# pixhawk.net
KiCad netlist of a schematic drawn in EAGLE
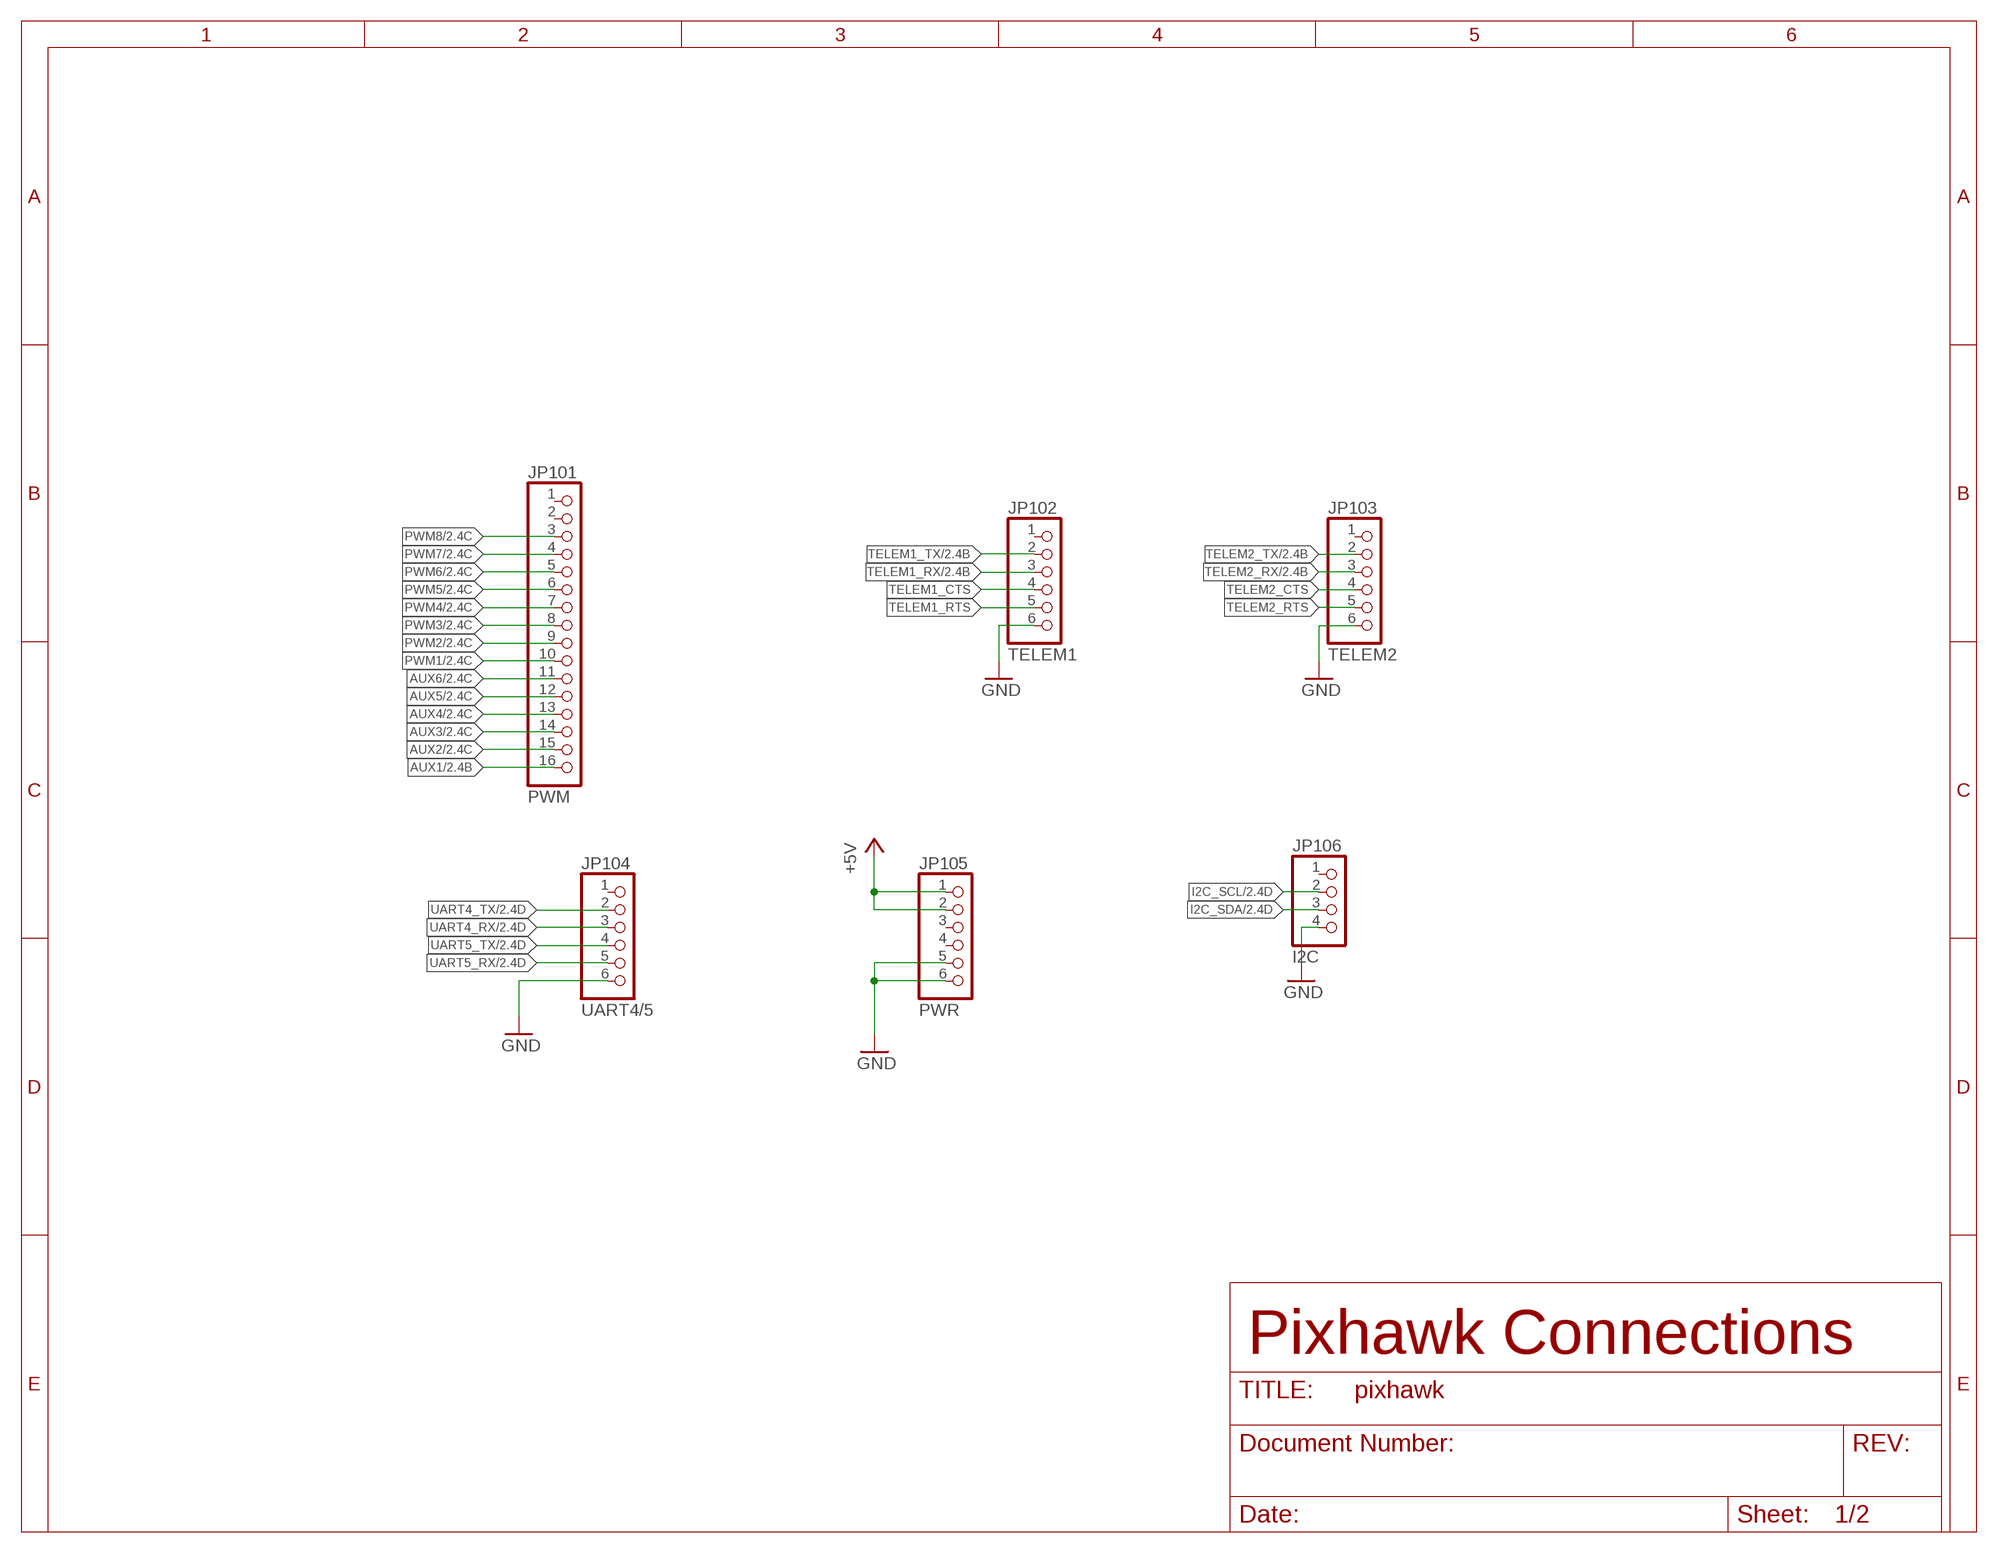
[diagram p0: schematic, sheet 1]
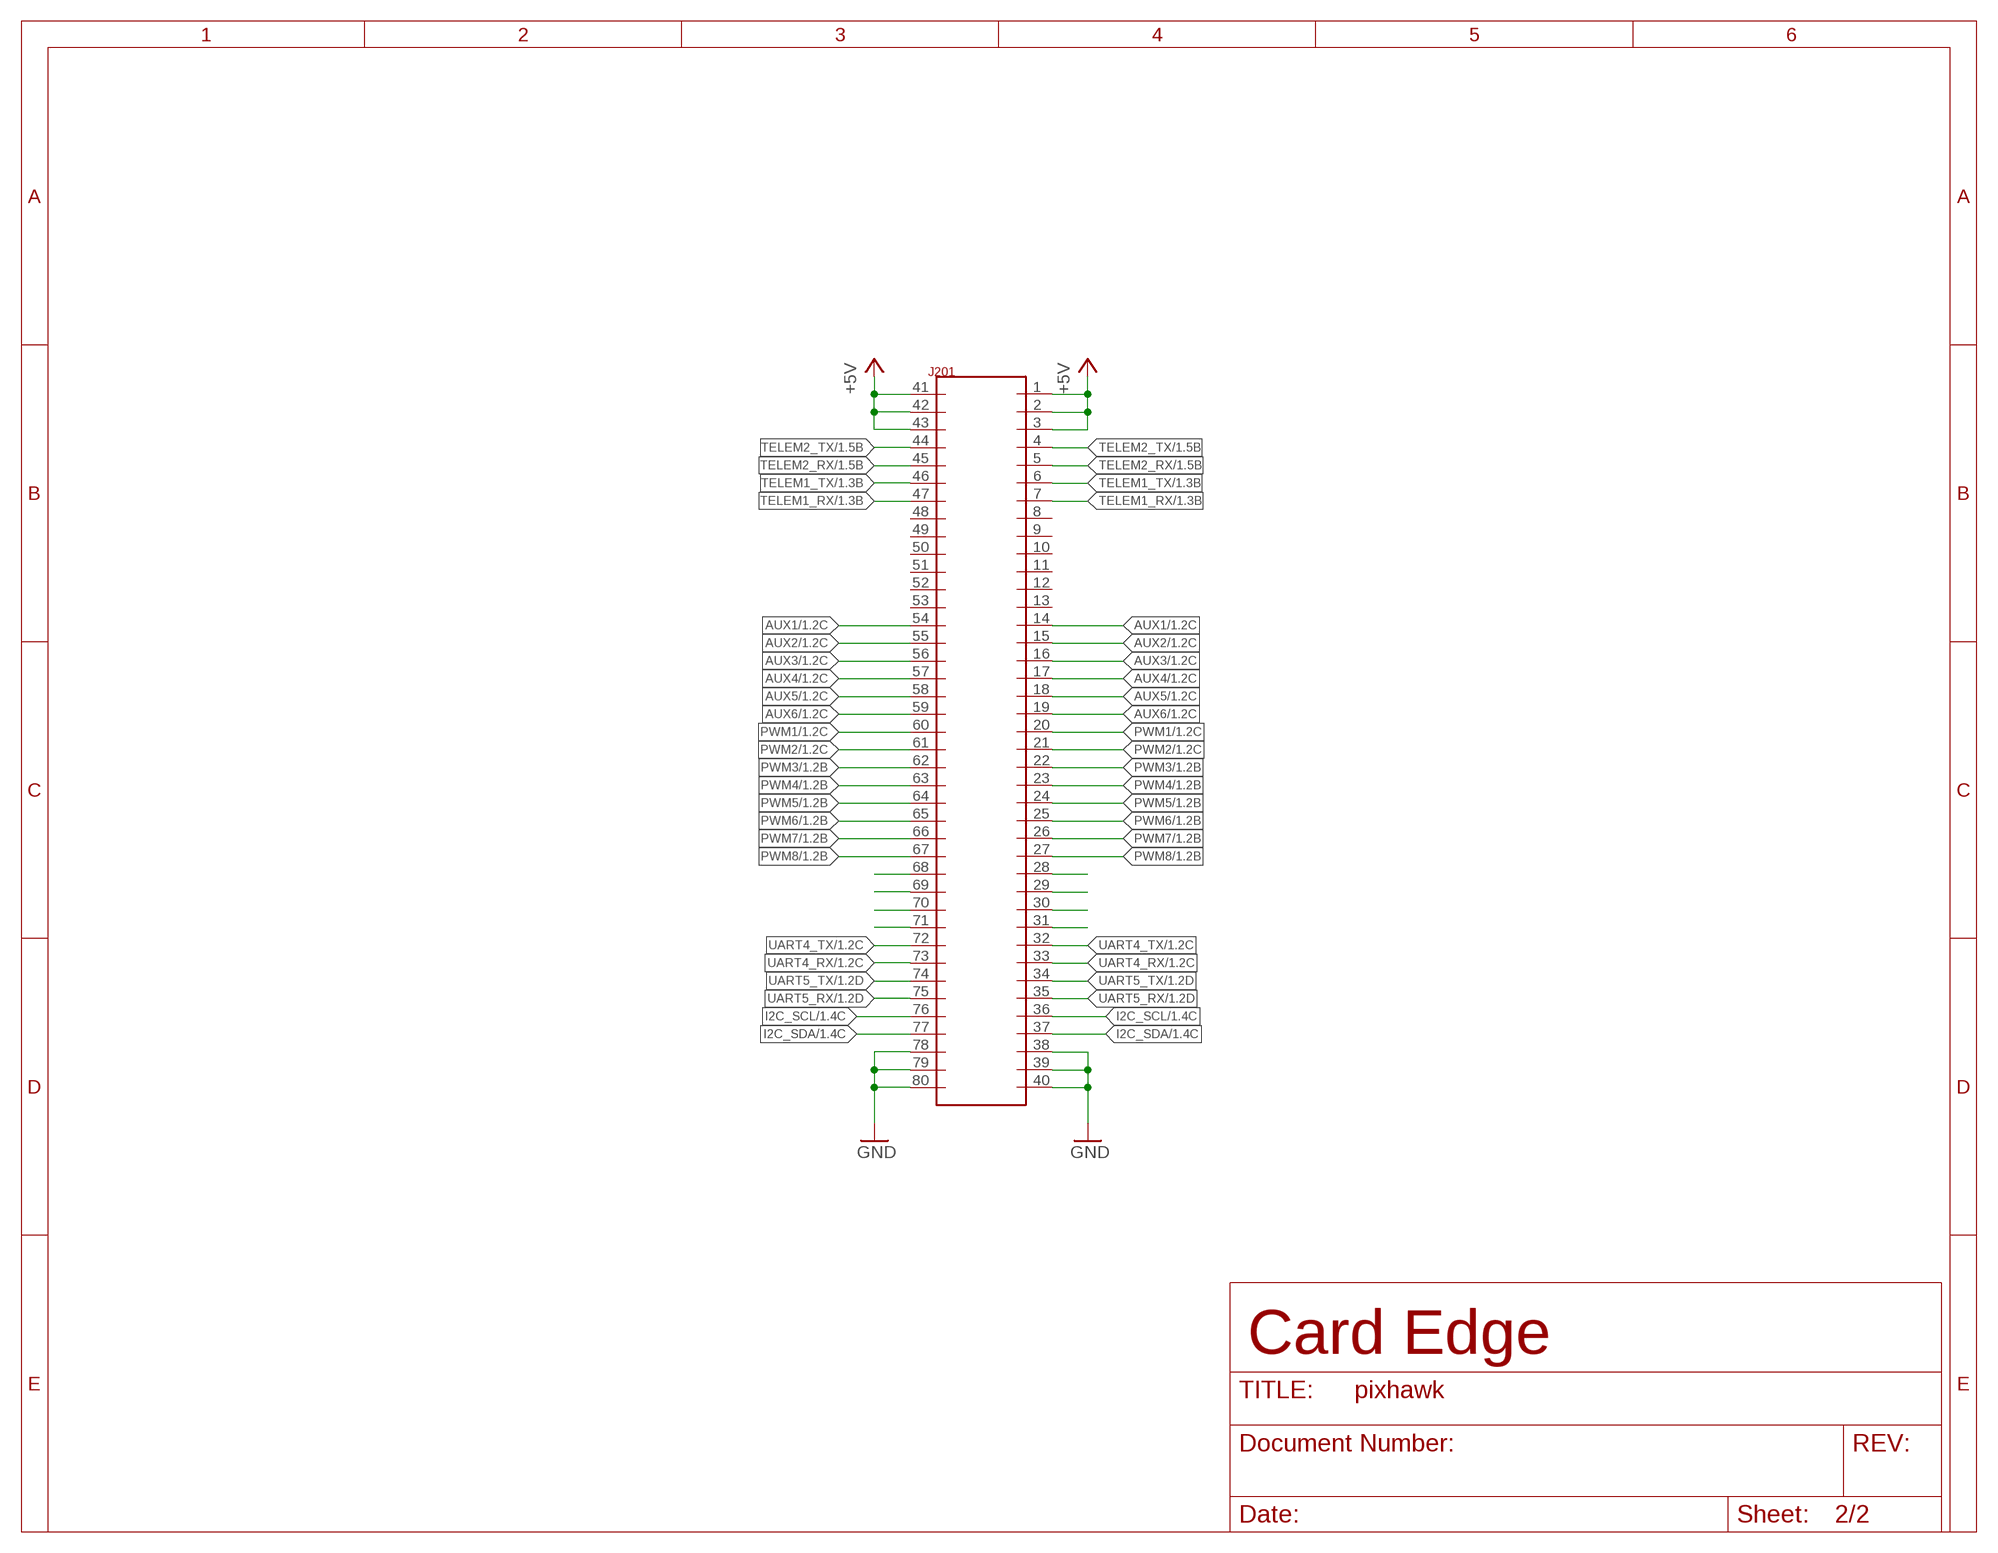
[diagram p1: schematic, sheet 2]

(export (version "E")
  (design (tool "Eeschema 10.0.6"))
  (components
    (comp (ref "J201")
      (value "80-PIN-CARD-EDGE")
      (footprint "eagle-import:80-PIN-CARD-EDGE")
      (libsource (lib "eagle-import") (part "80-PIN-CARD-EDGE"))
    )
    (comp (ref "JP101")
      (value "PWM")
      (footprint "eagle-import:1X16")
      (libsource (lib "eagle-import") (part "PINHD-1X16"))
    )
    (comp (ref "JP102")
      (value "TELEM1")
      (footprint "eagle-import:1X06")
      (libsource (lib "eagle-import") (part "PINHD-1X6"))
    )
    (comp (ref "JP103")
      (value "TELEM2")
      (footprint "eagle-import:1X06")
      (libsource (lib "eagle-import") (part "PINHD-1X6"))
    )
    (comp (ref "JP104")
      (value "UART4/5")
      (footprint "eagle-import:1X06")
      (libsource (lib "eagle-import") (part "PINHD-1X6"))
    )
    (comp (ref "JP105")
      (value "PWR")
      (footprint "eagle-import:1X06")
      (libsource (lib "eagle-import") (part "PINHD-1X6"))
    )
    (comp (ref "JP106")
      (value "I2C")
      (footprint "eagle-import:1X04")
      (libsource (lib "eagle-import") (part "PINHD-1X4"))
    )
  )
  (nets
    (net (code "1") (name "+5V") (class "Default")
      (node (ref "J201") (pin "1") (pinfunction "P$1_1") (pintype "bidirectional"))
      (node (ref "J201") (pin "2") (pinfunction "P$2_2") (pintype "bidirectional"))
      (node (ref "J201") (pin "3") (pinfunction "P$3_3") (pintype "bidirectional"))
      (node (ref "J201") (pin "41") (pinfunction "P$41_41") (pintype "bidirectional"))
      (node (ref "J201") (pin "42") (pinfunction "P$42_42") (pintype "bidirectional"))
      (node (ref "J201") (pin "43") (pinfunction "P$43_43") (pintype "bidirectional"))
      (node (ref "JP105") (pin "1") (pinfunction "1_1") (pintype "passive"))
      (node (ref "JP105") (pin "2") (pinfunction "2_2") (pintype "passive"))
    )
    (net (code "2") (name "AUX1") (class "Default")
      (node (ref "J201") (pin "14") (pinfunction "P$14_14") (pintype "bidirectional"))
      (node (ref "J201") (pin "54") (pinfunction "P$54_54") (pintype "bidirectional"))
      (node (ref "JP101") (pin "16") (pinfunction "16_16") (pintype "passive"))
    )
    (net (code "3") (name "AUX2") (class "Default")
      (node (ref "J201") (pin "15") (pinfunction "P$15_15") (pintype "bidirectional"))
      (node (ref "J201") (pin "55") (pinfunction "P$55_55") (pintype "bidirectional"))
      (node (ref "JP101") (pin "15") (pinfunction "15_15") (pintype "passive"))
    )
    (net (code "4") (name "AUX3") (class "Default")
      (node (ref "J201") (pin "16") (pinfunction "P$16_16") (pintype "bidirectional"))
      (node (ref "J201") (pin "56") (pinfunction "P$56_56") (pintype "bidirectional"))
      (node (ref "JP101") (pin "14") (pinfunction "14_14") (pintype "passive"))
    )
    (net (code "5") (name "AUX4") (class "Default")
      (node (ref "J201") (pin "17") (pinfunction "P$17_17") (pintype "bidirectional"))
      (node (ref "J201") (pin "57") (pinfunction "P$57_57") (pintype "bidirectional"))
      (node (ref "JP101") (pin "13") (pinfunction "13_13") (pintype "passive"))
    )
    (net (code "6") (name "AUX5") (class "Default")
      (node (ref "J201") (pin "18") (pinfunction "P$18_18") (pintype "bidirectional"))
      (node (ref "J201") (pin "58") (pinfunction "P$58_58") (pintype "bidirectional"))
      (node (ref "JP101") (pin "12") (pinfunction "12_12") (pintype "passive"))
    )
    (net (code "7") (name "AUX6") (class "Default")
      (node (ref "J201") (pin "19") (pinfunction "P$19_19") (pintype "bidirectional"))
      (node (ref "J201") (pin "59") (pinfunction "P$59_59") (pintype "bidirectional"))
      (node (ref "JP101") (pin "11") (pinfunction "11_11") (pintype "passive"))
    )
    (net (code "8") (name "CAN_H") (class "Default")
      (node (ref "J201") (pin "30") (pinfunction "P$30_30") (pintype "bidirectional"))
      (node (ref "J201") (pin "70") (pinfunction "P$70_70") (pintype "bidirectional"))
    )
    (net (code "9") (name "CAN_L") (class "Default")
      (node (ref "J201") (pin "31") (pinfunction "P$31_31") (pintype "bidirectional"))
      (node (ref "J201") (pin "71") (pinfunction "P$71_71") (pintype "bidirectional"))
    )
    (net (code "10") (name "GND") (class "Default")
      (node (ref "J201") (pin "38") (pinfunction "P$38_38") (pintype "bidirectional"))
      (node (ref "J201") (pin "39") (pinfunction "P$39_39") (pintype "bidirectional"))
      (node (ref "J201") (pin "40") (pinfunction "P$40_40") (pintype "bidirectional"))
      (node (ref "J201") (pin "78") (pinfunction "P$78_78") (pintype "bidirectional"))
      (node (ref "J201") (pin "79") (pinfunction "P$79_79") (pintype "bidirectional"))
      (node (ref "J201") (pin "80") (pinfunction "P$80_80") (pintype "bidirectional"))
      (node (ref "JP102") (pin "6") (pinfunction "6_6") (pintype "passive"))
      (node (ref "JP103") (pin "6") (pinfunction "6_6") (pintype "passive"))
      (node (ref "JP104") (pin "6") (pinfunction "6_6") (pintype "passive"))
      (node (ref "JP105") (pin "5") (pinfunction "5_5") (pintype "passive"))
      (node (ref "JP105") (pin "6") (pinfunction "6_6") (pintype "passive"))
      (node (ref "JP106") (pin "4") (pinfunction "4_4") (pintype "passive"))
    )
    (net (code "11") (name "I2C_SCL") (class "Default")
      (node (ref "J201") (pin "36") (pinfunction "P$36_36") (pintype "bidirectional"))
      (node (ref "J201") (pin "76") (pinfunction "P$76_76") (pintype "bidirectional"))
      (node (ref "JP106") (pin "2") (pinfunction "2_2") (pintype "passive"))
    )
    (net (code "12") (name "I2C_SDA") (class "Default")
      (node (ref "J201") (pin "37") (pinfunction "P$37_37") (pintype "bidirectional"))
      (node (ref "J201") (pin "77") (pinfunction "P$77_77") (pintype "bidirectional"))
      (node (ref "JP106") (pin "3") (pinfunction "3_3") (pintype "passive"))
    )
    (net (code "13") (name "PWM1") (class "Default")
      (node (ref "J201") (pin "20") (pinfunction "P$20_20") (pintype "bidirectional"))
      (node (ref "J201") (pin "60") (pinfunction "P$60_60") (pintype "bidirectional"))
      (node (ref "JP101") (pin "10") (pinfunction "10_10") (pintype "passive"))
    )
    (net (code "14") (name "PWM2") (class "Default")
      (node (ref "J201") (pin "21") (pinfunction "P$21_21") (pintype "bidirectional"))
      (node (ref "J201") (pin "61") (pinfunction "P$61_61") (pintype "bidirectional"))
      (node (ref "JP101") (pin "9") (pinfunction "9_9") (pintype "passive"))
    )
    (net (code "15") (name "PWM3") (class "Default")
      (node (ref "J201") (pin "22") (pinfunction "P$22_22") (pintype "bidirectional"))
      (node (ref "J201") (pin "62") (pinfunction "P$62_62") (pintype "bidirectional"))
      (node (ref "JP101") (pin "8") (pinfunction "8_8") (pintype "passive"))
    )
    (net (code "16") (name "PWM4") (class "Default")
      (node (ref "J201") (pin "23") (pinfunction "P$23_23") (pintype "bidirectional"))
      (node (ref "J201") (pin "63") (pinfunction "P$63_63") (pintype "bidirectional"))
      (node (ref "JP101") (pin "7") (pinfunction "7_7") (pintype "passive"))
    )
    (net (code "17") (name "PWM5") (class "Default")
      (node (ref "J201") (pin "24") (pinfunction "P$24_24") (pintype "bidirectional"))
      (node (ref "J201") (pin "64") (pinfunction "P$64_64") (pintype "bidirectional"))
      (node (ref "JP101") (pin "6") (pinfunction "6_6") (pintype "passive"))
    )
    (net (code "18") (name "PWM6") (class "Default")
      (node (ref "J201") (pin "25") (pinfunction "P$25_25") (pintype "bidirectional"))
      (node (ref "J201") (pin "65") (pinfunction "P$65_65") (pintype "bidirectional"))
      (node (ref "JP101") (pin "5") (pinfunction "5_5") (pintype "passive"))
    )
    (net (code "19") (name "PWM7") (class "Default")
      (node (ref "J201") (pin "26") (pinfunction "P$26_26") (pintype "bidirectional"))
      (node (ref "J201") (pin "66") (pinfunction "P$66_66") (pintype "bidirectional"))
      (node (ref "JP101") (pin "4") (pinfunction "4_4") (pintype "passive"))
    )
    (net (code "20") (name "PWM8") (class "Default")
      (node (ref "J201") (pin "27") (pinfunction "P$27_27") (pintype "bidirectional"))
      (node (ref "J201") (pin "67") (pinfunction "P$67_67") (pintype "bidirectional"))
      (node (ref "JP101") (pin "3") (pinfunction "3_3") (pintype "passive"))
    )
    (net (code "21") (name "TELEM1_CTS") (class "Default")
      (node (ref "JP102") (pin "4") (pinfunction "4_4") (pintype "passive"))
    )
    (net (code "22") (name "TELEM1_RTS") (class "Default")
      (node (ref "JP102") (pin "5") (pinfunction "5_5") (pintype "passive"))
    )
    (net (code "23") (name "TELEM1_RX") (class "Default")
      (node (ref "J201") (pin "47") (pinfunction "P$47_47") (pintype "bidirectional"))
      (node (ref "J201") (pin "7") (pinfunction "P$7_7") (pintype "bidirectional"))
      (node (ref "JP102") (pin "3") (pinfunction "3_3") (pintype "passive"))
    )
    (net (code "24") (name "TELEM1_TX") (class "Default")
      (node (ref "J201") (pin "46") (pinfunction "P$46_46") (pintype "bidirectional"))
      (node (ref "J201") (pin "6") (pinfunction "P$6_6") (pintype "bidirectional"))
      (node (ref "JP102") (pin "2") (pinfunction "2_2") (pintype "passive"))
    )
    (net (code "25") (name "TELEM2_CTS") (class "Default")
      (node (ref "JP103") (pin "4") (pinfunction "4_4") (pintype "passive"))
    )
    (net (code "26") (name "TELEM2_RTS") (class "Default")
      (node (ref "JP103") (pin "5") (pinfunction "5_5") (pintype "passive"))
    )
    (net (code "27") (name "TELEM2_RX") (class "Default")
      (node (ref "J201") (pin "45") (pinfunction "P$45_45") (pintype "bidirectional"))
      (node (ref "J201") (pin "5") (pinfunction "P$5_5") (pintype "bidirectional"))
      (node (ref "JP103") (pin "3") (pinfunction "3_3") (pintype "passive"))
    )
    (net (code "28") (name "TELEM2_TX") (class "Default")
      (node (ref "J201") (pin "4") (pinfunction "P$4_4") (pintype "bidirectional"))
      (node (ref "J201") (pin "44") (pinfunction "P$44_44") (pintype "bidirectional"))
      (node (ref "JP103") (pin "2") (pinfunction "2_2") (pintype "passive"))
    )
    (net (code "29") (name "UART4_RX") (class "Default")
      (node (ref "J201") (pin "33") (pinfunction "P$33_33") (pintype "bidirectional"))
      (node (ref "J201") (pin "73") (pinfunction "P$73_73") (pintype "bidirectional"))
      (node (ref "JP104") (pin "3") (pinfunction "3_3") (pintype "passive"))
    )
    (net (code "30") (name "UART4_TX") (class "Default")
      (node (ref "J201") (pin "32") (pinfunction "P$32_32") (pintype "bidirectional"))
      (node (ref "J201") (pin "72") (pinfunction "P$72_72") (pintype "bidirectional"))
      (node (ref "JP104") (pin "2") (pinfunction "2_2") (pintype "passive"))
    )
    (net (code "31") (name "UART5_RX") (class "Default")
      (node (ref "J201") (pin "35") (pinfunction "P$35_35") (pintype "bidirectional"))
      (node (ref "J201") (pin "75") (pinfunction "P$75_75") (pintype "bidirectional"))
      (node (ref "JP104") (pin "5") (pinfunction "5_5") (pintype "passive"))
    )
    (net (code "32") (name "UART5_TX") (class "Default")
      (node (ref "J201") (pin "34") (pinfunction "P$34_34") (pintype "bidirectional"))
      (node (ref "J201") (pin "74") (pinfunction "P$74_74") (pintype "bidirectional"))
      (node (ref "JP104") (pin "4") (pinfunction "4_4") (pintype "passive"))
    )
    (net (code "33") (name "unconnected-(J201-P$8-Pad8)") (class "Default")
      (node (ref "J201") (pin "8") (pinfunction "P$8_8") (pintype "bidirectional"))
    )
    (net (code "34") (name "unconnected-(J201-P$9-Pad9)") (class "Default")
      (node (ref "J201") (pin "9") (pinfunction "P$9_9") (pintype "bidirectional"))
    )
    (net (code "35") (name "unconnected-(J201-P$10-Pad10)") (class "Default")
      (node (ref "J201") (pin "10") (pinfunction "P$10_10") (pintype "bidirectional"))
    )
    (net (code "36") (name "unconnected-(J201-P$11-Pad11)") (class "Default")
      (node (ref "J201") (pin "11") (pinfunction "P$11_11") (pintype "bidirectional"))
    )
    (net (code "37") (name "unconnected-(J201-P$12-Pad12)") (class "Default")
      (node (ref "J201") (pin "12") (pinfunction "P$12_12") (pintype "bidirectional"))
    )
    (net (code "38") (name "unconnected-(J201-P$13-Pad13)") (class "Default")
      (node (ref "J201") (pin "13") (pinfunction "P$13_13") (pintype "bidirectional"))
    )
    (net (code "39") (name "unconnected-(J201-P$28-Pad28)") (class "Default")
      (node (ref "J201") (pin "28") (pinfunction "P$28_28") (pintype "bidirectional"))
    )
    (net (code "40") (name "unconnected-(J201-P$29-Pad29)") (class "Default")
      (node (ref "J201") (pin "29") (pinfunction "P$29_29") (pintype "bidirectional"))
    )
    (net (code "41") (name "unconnected-(J201-P$48-Pad48)") (class "Default")
      (node (ref "J201") (pin "48") (pinfunction "P$48_48") (pintype "bidirectional"))
    )
    (net (code "42") (name "unconnected-(J201-P$49-Pad49)") (class "Default")
      (node (ref "J201") (pin "49") (pinfunction "P$49_49") (pintype "bidirectional"))
    )
    (net (code "43") (name "unconnected-(J201-P$50-Pad50)") (class "Default")
      (node (ref "J201") (pin "50") (pinfunction "P$50_50") (pintype "bidirectional"))
    )
    (net (code "44") (name "unconnected-(J201-P$51-Pad51)") (class "Default")
      (node (ref "J201") (pin "51") (pinfunction "P$51_51") (pintype "bidirectional"))
    )
    (net (code "45") (name "unconnected-(J201-P$52-Pad52)") (class "Default")
      (node (ref "J201") (pin "52") (pinfunction "P$52_52") (pintype "bidirectional"))
    )
    (net (code "46") (name "unconnected-(J201-P$53-Pad53)") (class "Default")
      (node (ref "J201") (pin "53") (pinfunction "P$53_53") (pintype "bidirectional"))
    )
    (net (code "47") (name "unconnected-(J201-P$68-Pad68)") (class "Default")
      (node (ref "J201") (pin "68") (pinfunction "P$68_68") (pintype "bidirectional"))
    )
    (net (code "48") (name "unconnected-(J201-P$69-Pad69)") (class "Default")
      (node (ref "J201") (pin "69") (pinfunction "P$69_69") (pintype "bidirectional"))
    )
    (net (code "49") (name "unconnected-(JP101-Pad1)") (class "Default")
      (node (ref "JP101") (pin "1") (pinfunction "1_1") (pintype "passive"))
    )
    (net (code "50") (name "unconnected-(JP101-Pad2)") (class "Default")
      (node (ref "JP101") (pin "2") (pinfunction "2_2") (pintype "passive"))
    )
    (net (code "51") (name "unconnected-(JP102-Pad1)") (class "Default")
      (node (ref "JP102") (pin "1") (pinfunction "1_1") (pintype "passive"))
    )
    (net (code "52") (name "unconnected-(JP103-Pad1)") (class "Default")
      (node (ref "JP103") (pin "1") (pinfunction "1_1") (pintype "passive"))
    )
    (net (code "53") (name "unconnected-(JP104-Pad1)") (class "Default")
      (node (ref "JP104") (pin "1") (pinfunction "1_1") (pintype "passive"))
    )
    (net (code "54") (name "unconnected-(JP105-Pad3)") (class "Default")
      (node (ref "JP105") (pin "3") (pinfunction "3_3") (pintype "passive"))
    )
    (net (code "55") (name "unconnected-(JP105-Pad4)") (class "Default")
      (node (ref "JP105") (pin "4") (pinfunction "4_4") (pintype "passive"))
    )
    (net (code "56") (name "unconnected-(JP106-Pad1)") (class "Default")
      (node (ref "JP106") (pin "1") (pinfunction "1_1") (pintype "passive"))
    )
  )
)
